# Meshtastic-DIY_v1_05.net
KiCad netlist of a schematic drawn in EAGLE
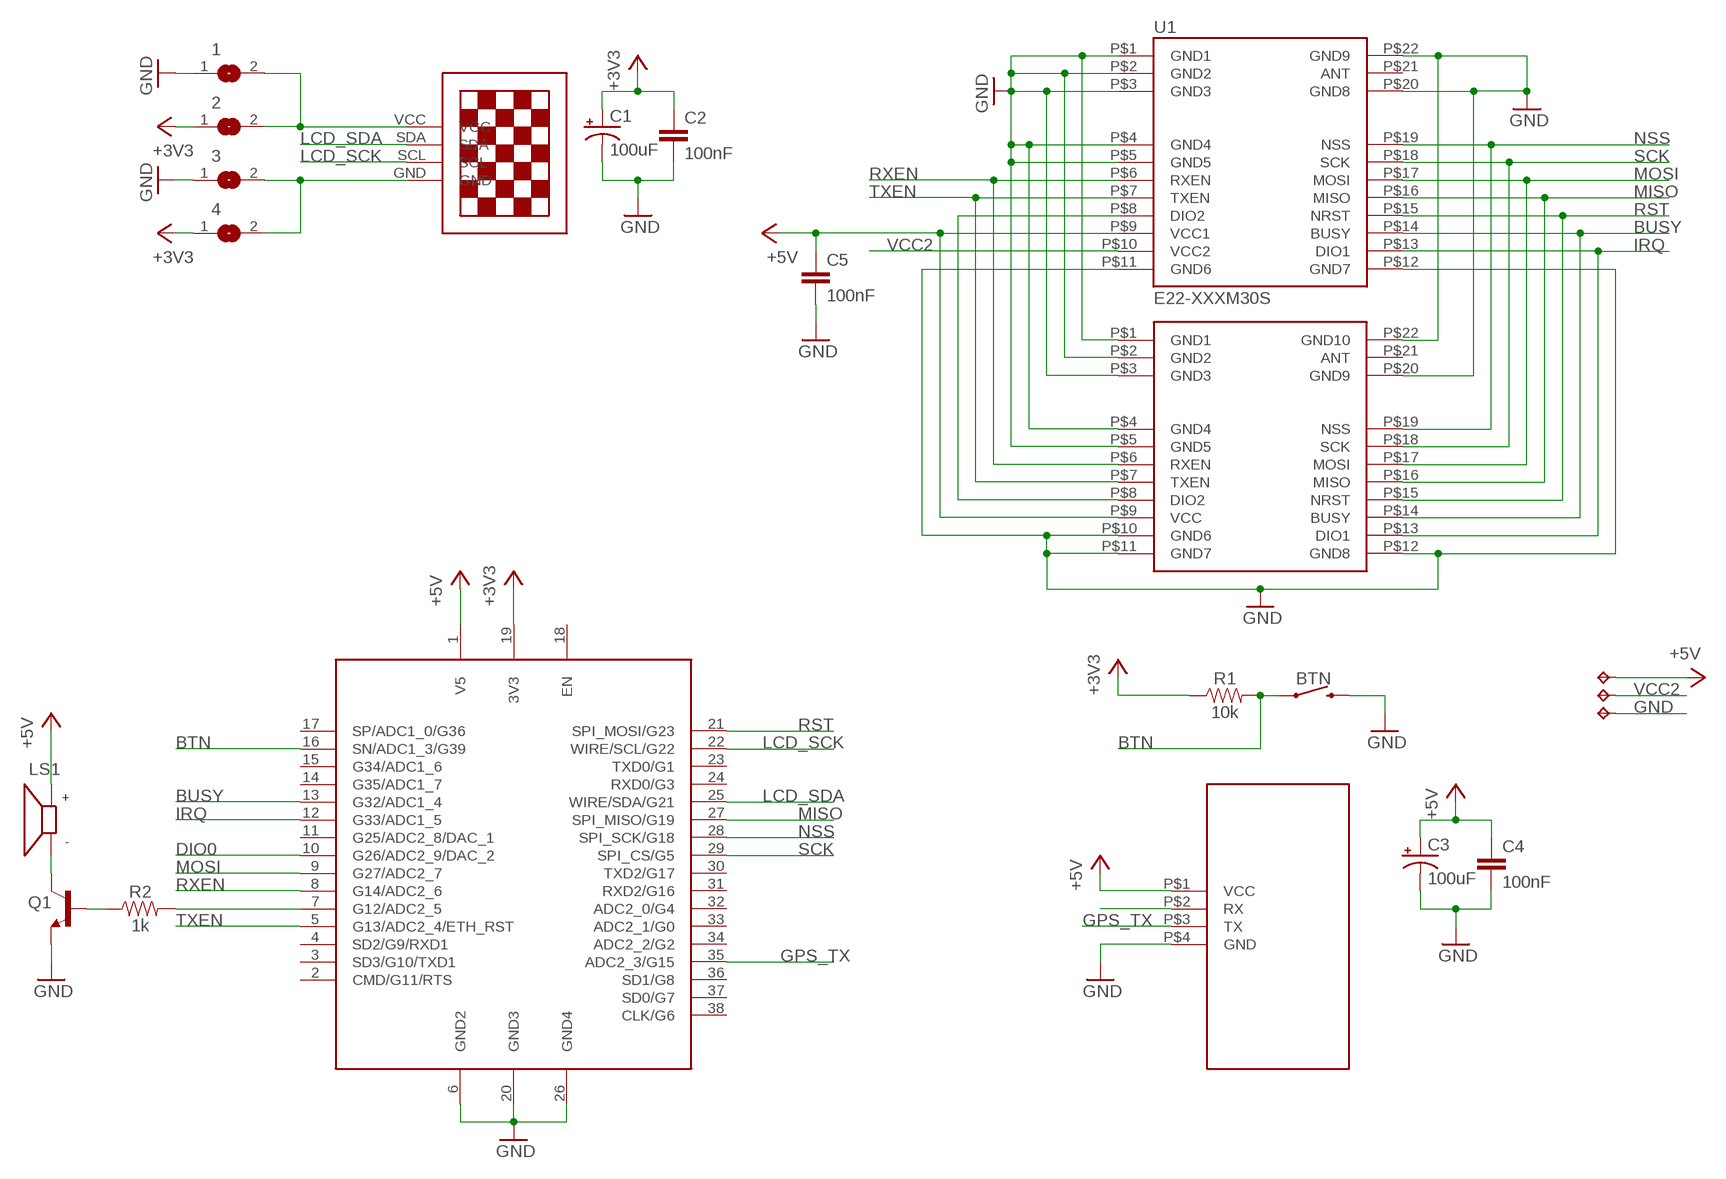
[diagram p0: schematic, sheet 1]

(export (version "E")
  (design (tool "Eeschema 10.0.6"))
  (components
    (comp (ref "1") (value "SJ") (footprint "eagle-import:SJ") (libsource (lib "eagle-import") (part "SJ")))
    (comp (ref "2") (value "SJ") (footprint "eagle-import:SJ") (libsource (lib "eagle-import") (part "SJ")))
    (comp (ref "3") (value "SJ") (footprint "eagle-import:SJ") (libsource (lib "eagle-import") (part "SJ")))
    (comp (ref "4") (value "SJ") (footprint "eagle-import:SJ") (libsource (lib "eagle-import") (part "SJ")))
    (comp (ref "BTN")
      (value "MOMENTARY-SWITCH-SPST-PTH-6.0MM")
      (footprint "eagle-import:TACTILE_SWITCH_PTH_6.0MM")
      (libsource (lib "eagle-import") (part "MOMENTARY-SWITCH-SPST-PTH-6.0MM"))
    )
    (comp (ref "C1")
      (value "100uF")
      (footprint "eagle-import:CPOL-RADIAL-2.5MM-6.5MM")
      (libsource (lib "eagle-import") (part "100UF-POLAR-RADIAL-2.5MM-25V-20%"))
    )
    (comp (ref "C2")
      (value "100nF")
      (footprint "eagle-import:0805")
      (libsource (lib "eagle-import") (part "0.33UF/330NF-0805-50V-10%"))
    )
    (comp (ref "C3")
      (value "100uF")
      (footprint "eagle-import:CPOL-RADIAL-2.5MM-6.5MM")
      (libsource (lib "eagle-import") (part "100UF-POLAR-RADIAL-2.5MM-25V-20%"))
    )
    (comp (ref "C4")
      (value "100nF")
      (footprint "eagle-import:0805")
      (libsource (lib "eagle-import") (part "0.33UF/330NF-0805-50V-10%"))
    )
    (comp (ref "C5")
      (value "100nF")
      (footprint "eagle-import:0805")
      (libsource (lib "eagle-import") (part "0.33UF/330NF-0805-50V-10%"))
    )
    (comp (ref "ESP32-1")
      (value "NODEMCU_ESP32_WROOM_32")
      (footprint "eagle-import:NODEMCU_ESP32_WROOM_32--38PINS")
      (libsource (lib "eagle-import") (part "NODEMCU_ESP32_WROOM_32"))
    )
    (comp (ref "LS1")
      (value "CMT-0926-86-SMT-TR")
      (footprint "eagle-import:XDCR_CMT-0926-86-SMT-TR")
      (fields (field (name "MF") "CUI Devices"))
      (libsource (lib "eagle-import") (part "CMT-0926-86-SMT-TR"))
    )
    (comp (ref "Q1")
      (value "200mA/40V")
      (footprint "eagle-import:TO-92")
      (libsource (lib "eagle-import") (part "TRANS_NPN-2N3904"))
    )
    (comp (ref "R1")
      (value "10k")
      (footprint "eagle-import:1210")
      (libsource (lib "eagle-import") (part "0.1OHM-1210-1/2W-1%"))
    )
    (comp (ref "R2")
      (value "1k")
      (footprint "eagle-import:1210")
      (libsource (lib "eagle-import") (part "0.1OHM-1210-1/2W-1%"))
    )
    (comp (ref "TP1")
      (value "TPTP14SQ")
      (footprint "eagle-import:TP14SQ")
      (libsource (lib "eagle-import") (part "TPTP14SQ"))
    )
    (comp (ref "TP2")
      (value "TPTP14SQ")
      (footprint "eagle-import:TP14SQ")
      (libsource (lib "eagle-import") (part "TPTP14SQ"))
    )
    (comp (ref "TP3")
      (value "TPTP14SQ")
      (footprint "eagle-import:TP14SQ")
      (libsource (lib "eagle-import") (part "TPTP14SQ"))
    )
    (comp (ref "U$1")
      (value "13\"OLED13\"OLED")
      (footprint "eagle-import:1.3_OLED")
      (libsource (lib "eagle-import") (part "13{dblquote}OLED13{dblquote}OLED"))
    )
    (comp (ref "U$2")
      (value "E22-XXXM22S")
      (footprint "eagle-import:E22-XXXM22S")
      (libsource (lib "eagle-import") (part "E22-XXXM22S"))
    )
    (comp (ref "U$3")
      (value "GPS-NEO")
      (footprint "eagle-import:GPS-NEO")
      (libsource (lib "eagle-import") (part "GPS-NEO"))
    )
    (comp (ref "U1")
      (value "E22-XXXM30S")
      (footprint "eagle-import:E22-XXXM30S")
      (libsource (lib "eagle-import") (part "E22-XXXM30S"))
    )
  )
  (nets
    (net (code "1") (name "+3V3") (class "Default")
      (node (ref "2") (pin "1") (pinfunction "1_1") (pintype "passive"))
      (node (ref "4") (pin "1") (pinfunction "1_1") (pintype "passive"))
      (node (ref "C1") (pin "1") (pinfunction "+_1") (pintype "passive"))
      (node (ref "C2") (pin "1") (pinfunction "1_1") (pintype "passive"))
      (node (ref "ESP32-1") (pin "19") (pinfunction "3V3_19") (pintype "power_in"))
      (node (ref "R1") (pin "1") (pinfunction "1_1") (pintype "passive"))
    )
    (net (code "2") (name "+5V") (class "Default")
      (node (ref "C3") (pin "1") (pinfunction "+_1") (pintype "passive"))
      (node (ref "C4") (pin "1") (pinfunction "1_1") (pintype "passive"))
      (node (ref "C5") (pin "1") (pinfunction "1_1") (pintype "passive"))
      (node (ref "ESP32-1") (pin "1") (pinfunction "V5_1") (pintype "power_in"))
      (node (ref "LS1") (pin "P") (pinfunction "P_P") (pintype "passive"))
      (node (ref "TP1") (pin "TP") (pinfunction "TP_TP") (pintype "input"))
      (node (ref "U$2") (pin "P$9") (pinfunction "VCC_P$9") (pintype "bidirectional"))
      (node (ref "U$3") (pin "P$1") (pinfunction "VCC_P$1") (pintype "bidirectional"))
      (node (ref "U1") (pin "P$9") (pinfunction "VCC1_P$9") (pintype "bidirectional"))
    )
    (net (code "3") (name "/BTN") (class "Default")
      (node (ref "BTN") (pin "1") (pinfunction "1_1") (pintype "passive"))
      (node (ref "ESP32-1") (pin "16") (pinfunction "SN/ADC1_3/G39_16") (pintype "bidirectional"))
      (node (ref "R1") (pin "2") (pinfunction "2_2") (pintype "passive"))
    )
    (net (code "4") (name "/BUSY") (class "Default")
      (node (ref "ESP32-1") (pin "13") (pinfunction "G32/ADC1_4_13") (pintype "bidirectional"))
      (node (ref "U$2") (pin "P$14") (pinfunction "BUSY_P$14") (pintype "bidirectional"))
      (node (ref "U1") (pin "P$14") (pinfunction "BUSY_P$14") (pintype "bidirectional"))
    )
    (net (code "5") (name "/CMD{slash}G11{slash}RTS") (class "Default")
      (node (ref "ESP32-1") (pin "2") (pinfunction "CMD/G11/RTS_2") (pintype "power_in"))
    )
    (net (code "6") (name "/DIO0") (class "Default")
      (node (ref "ESP32-1") (pin "10") (pinfunction "G26/ADC2_9/DAC_2_10") (pintype "bidirectional"))
    )
    (net (code "7") (name "/GPS_TX") (class "Default")
      (node (ref "ESP32-1") (pin "35") (pinfunction "ADC2_3/G15_35") (pintype "bidirectional"))
      (node (ref "U$3") (pin "P$3") (pinfunction "TX_P$3") (pintype "bidirectional"))
    )
    (net (code "8") (name "/IRQ") (class "Default")
      (node (ref "ESP32-1") (pin "12") (pinfunction "G33/ADC1_5_12") (pintype "bidirectional"))
      (node (ref "U$2") (pin "P$13") (pinfunction "DIO1_P$13") (pintype "bidirectional"))
      (node (ref "U1") (pin "P$13") (pinfunction "DIO1_P$13") (pintype "bidirectional"))
    )
    (net (code "9") (name "/LCD_SCK") (class "Default")
      (node (ref "ESP32-1") (pin "22") (pinfunction "WIRE/SCL/G22_22") (pintype "bidirectional"))
      (node (ref "U$1") (pin "SCL") (pinfunction "SCL_SCL") (pintype "bidirectional"))
    )
    (net (code "10") (name "/LCD_SDA") (class "Default")
      (node (ref "ESP32-1") (pin "25") (pinfunction "WIRE/SDA/G21_25") (pintype "bidirectional"))
      (node (ref "U$1") (pin "SDA") (pinfunction "SDA_SDA") (pintype "bidirectional"))
    )
    (net (code "11") (name "/MISO") (class "Default")
      (node (ref "ESP32-1") (pin "27") (pinfunction "SPI_MISO/G19_27") (pintype "bidirectional"))
      (node (ref "U$2") (pin "P$16") (pinfunction "MISO_P$16") (pintype "bidirectional"))
      (node (ref "U1") (pin "P$16") (pinfunction "MISO_P$16") (pintype "bidirectional"))
    )
    (net (code "12") (name "/MOSI") (class "Default")
      (node (ref "ESP32-1") (pin "9") (pinfunction "G27/ADC2_7_9") (pintype "bidirectional"))
      (node (ref "U$2") (pin "P$17") (pinfunction "MOSI_P$17") (pintype "bidirectional"))
      (node (ref "U1") (pin "P$17") (pinfunction "MOSI_P$17") (pintype "bidirectional"))
    )
    (net (code "13") (name "/NSS") (class "Default")
      (node (ref "ESP32-1") (pin "28") (pinfunction "SPI_SCK/G18_28") (pintype "bidirectional"))
      (node (ref "U$2") (pin "P$19") (pinfunction "NSS_P$19") (pintype "bidirectional"))
      (node (ref "U1") (pin "P$19") (pinfunction "NSS_P$19") (pintype "bidirectional"))
    )
    (net (code "14") (name "/RST") (class "Default")
      (node (ref "ESP32-1") (pin "21") (pinfunction "SPI_MOSI/G23_21") (pintype "bidirectional"))
      (node (ref "U$2") (pin "P$15") (pinfunction "NRST_P$15") (pintype "bidirectional"))
      (node (ref "U1") (pin "P$15") (pinfunction "NRST_P$15") (pintype "bidirectional"))
    )
    (net (code "15") (name "/RXEN") (class "Default")
      (node (ref "ESP32-1") (pin "8") (pinfunction "G14/ADC2_6_8") (pintype "bidirectional"))
      (node (ref "U$2") (pin "P$6") (pinfunction "RXEN_P$6") (pintype "bidirectional"))
      (node (ref "U1") (pin "P$6") (pinfunction "RXEN_P$6") (pintype "bidirectional"))
    )
    (net (code "16") (name "/SCK") (class "Default")
      (node (ref "ESP32-1") (pin "29") (pinfunction "SPI_CS/G5_29") (pintype "bidirectional"))
      (node (ref "U$2") (pin "P$18") (pinfunction "SCK_P$18") (pintype "bidirectional"))
      (node (ref "U1") (pin "P$18") (pinfunction "SCK_P$18") (pintype "bidirectional"))
    )
    (net (code "17") (name "/TXEN") (class "Default")
      (node (ref "ESP32-1") (pin "5") (pinfunction "G13/ADC2_4/ETH_RST_5") (pintype "bidirectional"))
      (node (ref "U$2") (pin "P$7") (pinfunction "TXEN_P$7") (pintype "bidirectional"))
      (node (ref "U1") (pin "P$7") (pinfunction "TXEN_P$7") (pintype "bidirectional"))
    )
    (net (code "18") (name "/VCC2") (class "Default")
      (node (ref "TP2") (pin "TP") (pinfunction "TP_TP") (pintype "input"))
      (node (ref "U1") (pin "P$10") (pinfunction "VCC2_P$10") (pintype "bidirectional"))
    )
    (net (code "19") (name "GND") (class "Default")
      (node (ref "1") (pin "1") (pinfunction "1_1") (pintype "passive"))
      (node (ref "3") (pin "1") (pinfunction "1_1") (pintype "passive"))
      (node (ref "BTN") (pin "3") (pinfunction "2_3") (pintype "passive"))
      (node (ref "C1") (pin "2") (pinfunction "-_2") (pintype "passive"))
      (node (ref "C2") (pin "2") (pinfunction "2_2") (pintype "passive"))
      (node (ref "C3") (pin "2") (pinfunction "-_2") (pintype "passive"))
      (node (ref "C4") (pin "2") (pinfunction "2_2") (pintype "passive"))
      (node (ref "C5") (pin "2") (pinfunction "2_2") (pintype "passive"))
      (node (ref "ESP32-1") (pin "20") (pinfunction "GND3_20") (pintype "power_in"))
      (node (ref "ESP32-1") (pin "26") (pinfunction "GND4_26") (pintype "power_in"))
      (node (ref "ESP32-1") (pin "6") (pinfunction "GND2_6") (pintype "power_in"))
      (node (ref "Q1") (pin "1") (pinfunction "E_1") (pintype "passive"))
      (node (ref "TP3") (pin "TP") (pinfunction "TP_TP") (pintype "input"))
      (node (ref "U$2") (pin "P$1") (pinfunction "GND1_P$1") (pintype "bidirectional"))
      (node (ref "U$2") (pin "P$10") (pinfunction "GND6_P$10") (pintype "bidirectional"))
      (node (ref "U$2") (pin "P$11") (pinfunction "GND7_P$11") (pintype "bidirectional"))
      (node (ref "U$2") (pin "P$12") (pinfunction "GND8_P$12") (pintype "bidirectional"))
      (node (ref "U$2") (pin "P$2") (pinfunction "GND2_P$2") (pintype "bidirectional"))
      (node (ref "U$2") (pin "P$20") (pinfunction "GND9_P$20") (pintype "bidirectional"))
      (node (ref "U$2") (pin "P$22") (pinfunction "GND10_P$22") (pintype "bidirectional"))
      (node (ref "U$2") (pin "P$3") (pinfunction "GND3_P$3") (pintype "bidirectional"))
      (node (ref "U$2") (pin "P$4") (pinfunction "GND4_P$4") (pintype "bidirectional"))
      (node (ref "U$2") (pin "P$5") (pinfunction "GND5_P$5") (pintype "bidirectional"))
      (node (ref "U$3") (pin "P$4") (pinfunction "GND_P$4") (pintype "bidirectional"))
      (node (ref "U1") (pin "P$1") (pinfunction "GND1_P$1") (pintype "bidirectional"))
      (node (ref "U1") (pin "P$11") (pinfunction "GND6_P$11") (pintype "bidirectional"))
      (node (ref "U1") (pin "P$12") (pinfunction "GND7_P$12") (pintype "bidirectional"))
      (node (ref "U1") (pin "P$2") (pinfunction "GND2_P$2") (pintype "bidirectional"))
      (node (ref "U1") (pin "P$20") (pinfunction "GND8_P$20") (pintype "bidirectional"))
      (node (ref "U1") (pin "P$22") (pinfunction "GND9_P$22") (pintype "bidirectional"))
      (node (ref "U1") (pin "P$3") (pinfunction "GND3_P$3") (pintype "bidirectional"))
      (node (ref "U1") (pin "P$4") (pinfunction "GND4_P$4") (pintype "bidirectional"))
      (node (ref "U1") (pin "P$5") (pinfunction "GND5_P$5") (pintype "bidirectional"))
    )
    (net (code "20") (name "Net-(1-Pad2)") (class "Default")
      (node (ref "1") (pin "2") (pinfunction "2_2") (pintype "passive"))
      (node (ref "2") (pin "2") (pinfunction "2_2") (pintype "passive"))
      (node (ref "U$1") (pin "VCC") (pinfunction "VCC_VCC") (pintype "bidirectional"))
    )
    (net (code "21") (name "Net-(3-Pad2)") (class "Default")
      (node (ref "3") (pin "2") (pinfunction "2_2") (pintype "passive"))
      (node (ref "4") (pin "2") (pinfunction "2_2") (pintype "passive"))
      (node (ref "U$1") (pin "GND") (pinfunction "GND_GND") (pintype "bidirectional"))
    )
    (net (code "22") (name "Net-(ESP32-1-G12{slash}ADC2_5)") (class "Default")
      (node (ref "ESP32-1") (pin "7") (pinfunction "G12/ADC2_5_7") (pintype "bidirectional"))
      (node (ref "R2") (pin "2") (pinfunction "2_2") (pintype "passive"))
    )
    (net (code "23") (name "Net-(Q1-B)") (class "Default")
      (node (ref "Q1") (pin "2") (pinfunction "B_2") (pintype "passive"))
      (node (ref "R2") (pin "1") (pinfunction "1_1") (pintype "passive"))
    )
    (net (code "24") (name "Net-(Q1-C)") (class "Default")
      (node (ref "LS1") (pin "N") (pinfunction "N_N") (pintype "passive"))
      (node (ref "Q1") (pin "3") (pinfunction "C_3") (pintype "passive"))
    )
    (net (code "25") (name "Net-(U$2-DIO2)") (class "Default")
      (node (ref "U$2") (pin "P$8") (pinfunction "DIO2_P$8") (pintype "bidirectional"))
      (node (ref "U1") (pin "P$8") (pinfunction "DIO2_P$8") (pintype "bidirectional"))
    )
    (net (code "26") (name "unconnected-(ESP32-1-ADC2_0{slash}G4-Pad32)") (class "Default")
      (node (ref "ESP32-1") (pin "32") (pinfunction "ADC2_0/G4_32") (pintype "bidirectional"))
    )
    (net (code "27") (name "unconnected-(ESP32-1-ADC2_1{slash}G0-Pad33)") (class "Default")
      (node (ref "ESP32-1") (pin "33") (pinfunction "ADC2_1/G0_33") (pintype "bidirectional"))
    )
    (net (code "28") (name "unconnected-(ESP32-1-ADC2_2{slash}G2-Pad34)") (class "Default")
      (node (ref "ESP32-1") (pin "34") (pinfunction "ADC2_2/G2_34") (pintype "bidirectional"))
    )
    (net (code "29") (name "unconnected-(ESP32-1-CLK{slash}G6-Pad38)") (class "Default")
      (node (ref "ESP32-1") (pin "38") (pinfunction "CLK/G6_38") (pintype "bidirectional"))
    )
    (net (code "30") (name "unconnected-(ESP32-1-EN-Pad18)") (class "Default")
      (node (ref "ESP32-1") (pin "18") (pinfunction "EN_18") (pintype "bidirectional"))
    )
    (net (code "31") (name "unconnected-(ESP32-1-G25{slash}ADC2_8{slash}DAC_1-Pad11)") (class "Default")
      (node (ref "ESP32-1") (pin "11") (pinfunction "G25/ADC2_8/DAC_1_11") (pintype "bidirectional"))
    )
    (net (code "32") (name "unconnected-(ESP32-1-G34{slash}ADC1_6-Pad15)") (class "Default")
      (node (ref "ESP32-1") (pin "15") (pinfunction "G34/ADC1_6_15") (pintype "bidirectional"))
    )
    (net (code "33") (name "unconnected-(ESP32-1-G35{slash}ADC1_7-Pad14)") (class "Default")
      (node (ref "ESP32-1") (pin "14") (pinfunction "G35/ADC1_7_14") (pintype "bidirectional"))
    )
    (net (code "34") (name "unconnected-(ESP32-1-RXD0{slash}G3-Pad24)") (class "Default")
      (node (ref "ESP32-1") (pin "24") (pinfunction "RXD0/G3_24") (pintype "bidirectional"))
    )
    (net (code "35") (name "unconnected-(ESP32-1-RXD2{slash}G16-Pad31)") (class "Default")
      (node (ref "ESP32-1") (pin "31") (pinfunction "RXD2/G16_31") (pintype "bidirectional"))
    )
    (net (code "36") (name "unconnected-(ESP32-1-SD0{slash}G7-Pad37)") (class "Default")
      (node (ref "ESP32-1") (pin "37") (pinfunction "SD0/G7_37") (pintype "bidirectional"))
    )
    (net (code "37") (name "unconnected-(ESP32-1-SD1{slash}G8-Pad36)") (class "Default")
      (node (ref "ESP32-1") (pin "36") (pinfunction "SD1/G8_36") (pintype "bidirectional"))
    )
    (net (code "38") (name "unconnected-(ESP32-1-SD2{slash}G9{slash}RXD1-Pad4)") (class "Default")
      (node (ref "ESP32-1") (pin "4") (pinfunction "SD2/G9/RXD1_4") (pintype "bidirectional"))
    )
    (net (code "39") (name "unconnected-(ESP32-1-SD3{slash}G10{slash}TXD1-Pad3)") (class "Default")
      (node (ref "ESP32-1") (pin "3") (pinfunction "SD3/G10/TXD1_3") (pintype "bidirectional"))
    )
    (net (code "40") (name "unconnected-(ESP32-1-SP{slash}ADC1_0{slash}G36-Pad17)") (class "Default")
      (node (ref "ESP32-1") (pin "17") (pinfunction "SP/ADC1_0/G36_17") (pintype "bidirectional"))
    )
    (net (code "41") (name "unconnected-(ESP32-1-TXD0{slash}G1-Pad23)") (class "Default")
      (node (ref "ESP32-1") (pin "23") (pinfunction "TXD0/G1_23") (pintype "bidirectional"))
    )
    (net (code "42") (name "unconnected-(ESP32-1-TXD2{slash}G17-Pad30)") (class "Default")
      (node (ref "ESP32-1") (pin "30") (pinfunction "TXD2/G17_30") (pintype "bidirectional"))
    )
    (net (code "43") (name "unconnected-(U$2-ANT-PadP$21)") (class "Default")
      (node (ref "U$2") (pin "P$21") (pinfunction "ANT_P$21") (pintype "bidirectional"))
    )
    (net (code "44") (name "unconnected-(U$3-RX-PadP$2)") (class "Default")
      (node (ref "U$3") (pin "P$2") (pinfunction "RX_P$2") (pintype "bidirectional"))
    )
    (net (code "45") (name "unconnected-(U1-ANT-PadP$21)") (class "Default")
      (node (ref "U1") (pin "P$21") (pinfunction "ANT_P$21") (pintype "bidirectional"))
    )
  )
)
